# H0AR3_Backend.net
KiCad netlist of a schematic drawn in Altium Designer
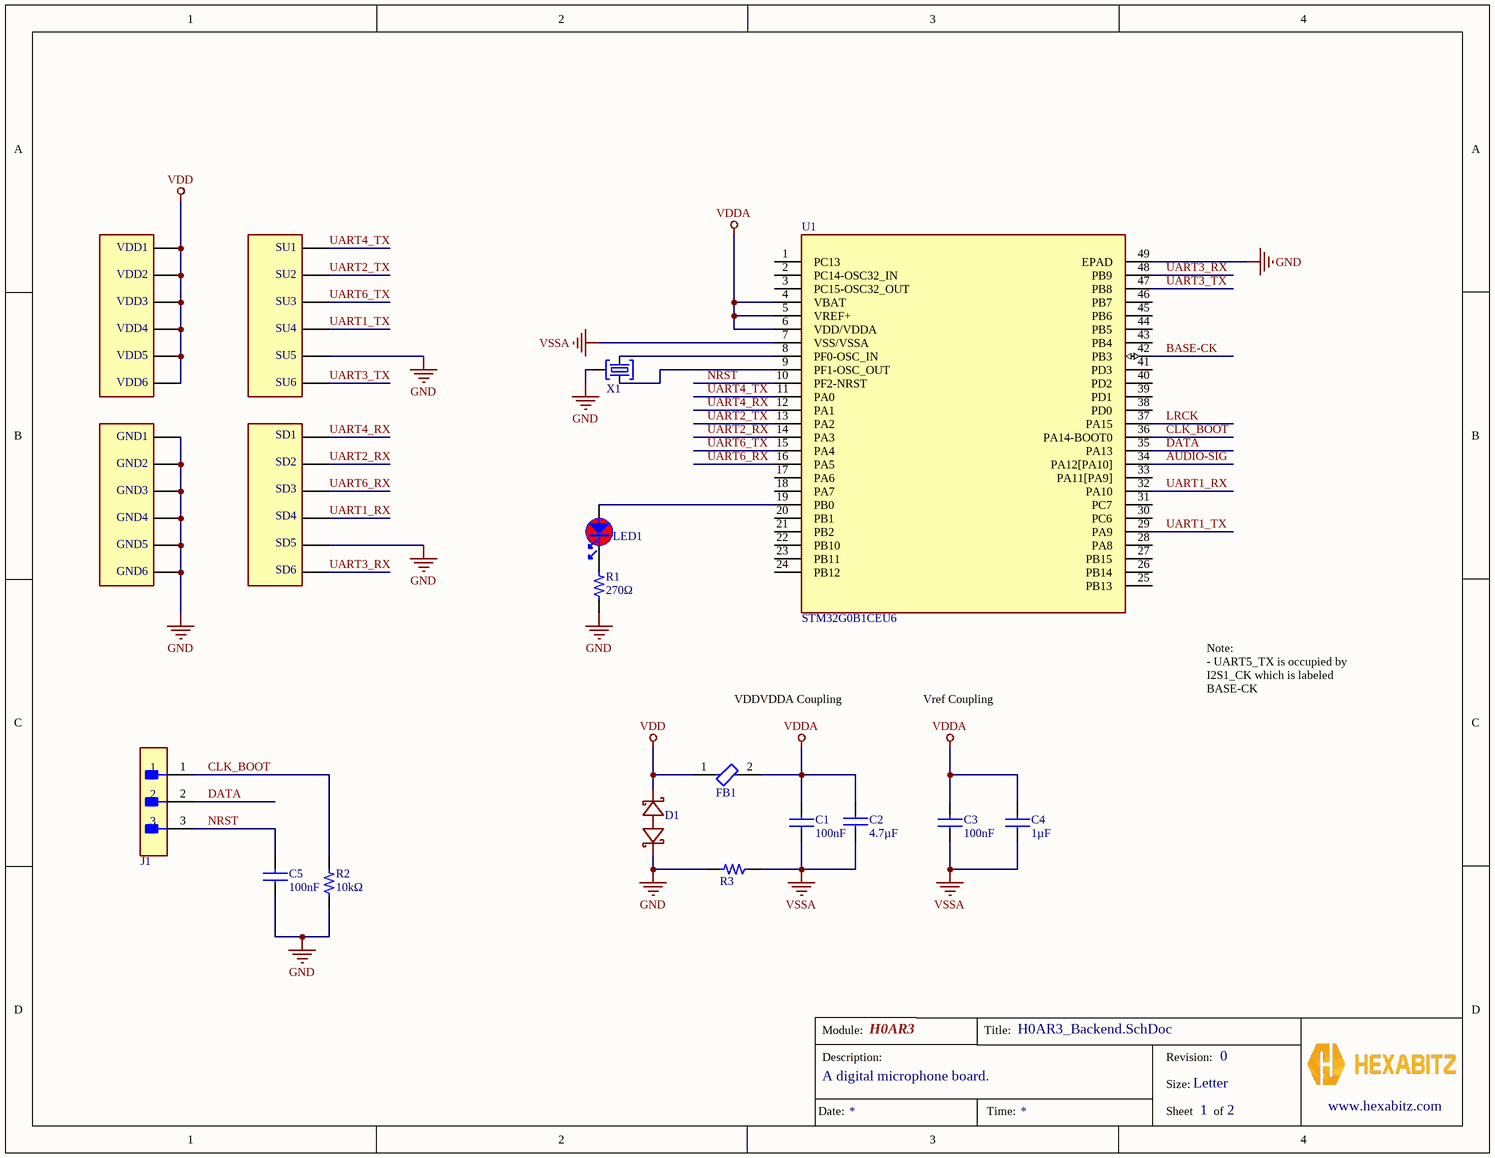
[diagram p0: H0AR3_Backend.SchDoc]

(export (version "E")
  (design (tool "Eeschema 10.0.6"))
  (components
    (comp (ref "C1")
      (value "100nF")
      (footprint "C0603")
      (fields
        (field (name "MANUFACTURER") "Samsung Electro-Mechanics")
        (field (name "MANUFACTURER PART NUMBER") "CL10B104KA8NNNC")
        (field (name "TOLERANCE") "10%")
      )
      (libsource (lib "Hexabitz Altium Library") (part "generic Capacitor"))
    )
    (comp (ref "C2")
      (value "4.7µF")
      (footprint "C0805")
      (fields
        (field (name "MANUFACTURER") "Samsung Electro-Mechanics")
        (field (name "MANUFACTURER PART NUMBER") "CL21X475KAQNNNE")
        (field (name "TOLERANCE") "10%")
      )
      (libsource (lib "Hexabitz Altium Library") (part "generic Capacitor"))
    )
    (comp (ref "C3")
      (value "100nF")
      (footprint "C0603")
      (fields
        (field (name "MANUFACTURER") "Samsung Electro-Mechanics")
        (field (name "MANUFACTURER PART NUMBER") "CL10B104KA8NNNC")
        (field (name "TOLERANCE") "10%")
      )
      (libsource (lib "Hexabitz Altium Library") (part "generic Capacitor"))
    )
    (comp (ref "C4")
      (value "1µF")
      (footprint "C0805")
      (description "Ceramic Capacitor, Ceramic, 16V, 10% +Tol, 10% -Tol, X7R, 15% TC, 1uF, Surface Mount, 0805")
      (fields
        (field (name "MANUFACTURER") "Yageo Group")
        (field (name "MANUFACTURER PART NUMBER") "CC0805KKX7R7BB105")
      )
      (libsource (lib "Hexabitz Altium Library") (part "generic Capacitor"))
    )
    (comp (ref "C5")
      (value "100nF")
      (footprint "C0603")
      (fields
        (field (name "MANUFACTURER") "Samsung Electro-Mechanics")
        (field (name "MANUFACTURER PART NUMBER") "CL10B104KA8NNNC")
        (field (name "TOLERANCE") "10%")
      )
      (libsource (lib "Hexabitz Altium Library") (part "generic Capacitor"))
    )
    (comp (ref "D1")
      (value "CDSOD323-T03SC")
      (footprint "SOD2513X114N")
      (description "A 3V, 350W, bi-directional, standard capacitance, SOD323 pkg TVS Diode ¦ Bourns CDSOD323-T03SC")
      (fields (field (name "MANUFACTURER") "Bourns"))
      (libsource (lib "Hexabitz Altium Library") (part "CDSOD323-T03SC"))
    )
    (comp (ref "FB1")
      (value "MMZ1608Y300B")
      (footprint "FP-MMZ1608-0_8-MFG")
      (description "Ferrite Beads 0603 30ohms 1500mA Signal Line AEC-Q200")
      (fields
        (field (name "MANUFACTURER") "TDK")
        (field (name "MANUFACTURER PART NUMBER") "MMZ1608Y300BTD25")
      )
      (libsource (lib "Hexabitz Altium Library") (part "MMZ1608Y300B"))
    )
    (comp (ref "GND1")
      (value "HEXABIT_UART_PORT")
      (footprint "HEXABIT_POWER_PORT_D")
      (libsource (lib "hexabitz_connectors.Library") (part "HEXABIT_POWER_PORT_D"))
    )
    (comp (ref "GND2")
      (value "HEXABIT_UART_PORT")
      (footprint "HEXABIT_POWER_PORT_D")
      (libsource (lib "hexabitz_connectors.Library") (part "HEXABIT_POWER_PORT_D"))
    )
    (comp (ref "GND3")
      (value "HEXABIT_UART_PORT")
      (footprint "HEXABIT_POWER_PORT_D")
      (libsource (lib "hexabitz_connectors.Library") (part "HEXABIT_POWER_PORT_D"))
    )
    (comp (ref "GND4")
      (value "HEXABIT_UART_PORT")
      (footprint "HEXABIT_POWER_PORT_D")
      (libsource (lib "hexabitz_connectors.Library") (part "HEXABIT_POWER_PORT_D"))
    )
    (comp (ref "GND5")
      (value "HEXABIT_UART_PORT")
      (footprint "HEXABIT_POWER_PORT_D")
      (libsource (lib "hexabitz_connectors.Library") (part "HEXABIT_POWER_PORT_D"))
    )
    (comp (ref "GND6")
      (value "HEXABIT_UART_PORT")
      (footprint "HEXABIT_POWER_PORT_D")
      (libsource (lib "hexabitz_connectors.Library") (part "HEXABIT_POWER_PORT_D"))
    )
    (comp (ref "J1")
      (value "TSW-103-14-G-S")
      (footprint "FP-TSW-103-14-G-S-MFG")
      (description "CONN HEADER VERT 3POS 2.54MM")
      (libsource (lib "Altium Content Vault") (part "cd3439d6ef35ae5d9b27ec4fdd3e828"))
    )
    (comp (ref "LED1")
      (value "VLMS1300-GS08")
      (footprint "FP-6_541-5092_01-4-MFG")
      (description "LED Uni-Color Super Red 639nm 2-Pin Chip 0603(1608Metric) T/R")
      (fields (field (name "MANUFACTURER") "Vishay Semiconductors"))
      (libsource (lib "Hexabitz Altium Library") (part "VLMS1300-GS08"))
    )
    (comp (ref "R1")
      (value "270Ω")
      (footprint "R0603")
      (description "Res Thick Film 0603 270 Ohm 5% 0.1W(1/10W) ±200ppm/C Pad SMD Automotive T/R")
      (fields
        (field (name "MANUFACTURER") "Panasonic")
        (field (name "MANUFACTURER PART NUMBER") "ERJ-3GEYJ271V")
      )
      (libsource (lib "") (part "generic Resistor_2"))
    )
    (comp (ref "R2")
      (value "10kΩ")
      (footprint "R0603")
      (description "100mW Thick Film Resistors ±100ppm/℃ ±1% 10kΩ 0603 Chip Resistor - Surface Mount ROHS")
      (fields
        (field (name "MANUFACTURER") "Yageo Group")
        (field (name "MANUFACTURER PART NUMBER") "RC0603FR-0710KL")
      )
      (libsource (lib "Hexabitz Altium Library") (part "generic Resistor"))
    )
    (comp (ref "R3")
      (value "Manufacturer Part Number")
      (footprint "R0603")
      (libsource (lib "") (part "generic Resistor_1"))
    )
    (comp (ref "SD1")
      (value "HEXABIT_UART_PORT")
      (footprint "HEXABIT_UART_PORT_D")
      (libsource (lib "hexabitz_connectors.Library") (part "HEXABIT_UART_PORT_D"))
    )
    (comp (ref "SD2")
      (value "HEXABIT_UART_PORT")
      (footprint "HEXABIT_UART_PORT_D")
      (libsource (lib "hexabitz_connectors.Library") (part "HEXABIT_UART_PORT_D"))
    )
    (comp (ref "SD3")
      (value "HEXABIT_UART_PORT")
      (footprint "HEXABIT_UART_PORT_D")
      (libsource (lib "hexabitz_connectors.Library") (part "HEXABIT_UART_PORT_D"))
    )
    (comp (ref "SD4")
      (value "HEXABIT_UART_PORT")
      (footprint "HEXABIT_UART_PORT_D")
      (libsource (lib "hexabitz_connectors.Library") (part "HEXABIT_UART_PORT_D"))
    )
    (comp (ref "SD5")
      (value "HEXABIT_UART_PORT")
      (footprint "HEXABIT_UART_PORT_D")
      (libsource (lib "hexabitz_connectors.Library") (part "HEXABIT_UART_PORT_D"))
    )
    (comp (ref "SD6")
      (value "HEXABIT_UART_PORT")
      (footprint "HEXABIT_UART_PORT_D")
      (libsource (lib "hexabitz_connectors.Library") (part "HEXABIT_UART_PORT_D"))
    )
    (comp (ref "SU1")
      (value "HEXABIT_UART_PORT")
      (footprint "HEXABIT_UART_PORT_U")
      (libsource (lib "hexabitz_connectors.Library") (part "HEXABIT_UART_PORT_U"))
    )
    (comp (ref "SU2")
      (value "HEXABIT_UART_PORT")
      (footprint "HEXABIT_UART_PORT_U")
      (libsource (lib "hexabitz_connectors.Library") (part "HEXABIT_UART_PORT_U"))
    )
    (comp (ref "SU3")
      (value "HEXABIT_UART_PORT")
      (footprint "HEXABIT_UART_PORT_U")
      (libsource (lib "hexabitz_connectors.Library") (part "HEXABIT_UART_PORT_U"))
    )
    (comp (ref "SU4")
      (value "HEXABIT_UART_PORT")
      (footprint "HEXABIT_UART_PORT_U")
      (libsource (lib "hexabitz_connectors.Library") (part "HEXABIT_UART_PORT_U"))
    )
    (comp (ref "SU5")
      (value "HEXABIT_UART_PORT")
      (footprint "HEXABIT_UART_PORT_U")
      (libsource (lib "hexabitz_connectors.Library") (part "HEXABIT_UART_PORT_U"))
    )
    (comp (ref "SU6")
      (value "HEXABIT_UART_PORT")
      (footprint "HEXABIT_UART_PORT_U")
      (libsource (lib "hexabitz_connectors.Library") (part "HEXABIT_UART_PORT_U"))
    )
    (comp (ref "U1")
      (value "STM32G0B1CEU6")
      (footprint "QFN50P700X700X65-49N-D")
      (description "MCU 32-bit ARM Cortex M0+ RISC 512KB Flash 1.8V/2.5V/3.3V 48-Pin UFQFPN EP Tray")
      (fields
        (field (name "MANUFACTURER") "STMicroelectronics")
        (field (name "MANUFACTURER PART NUMBER") "STM32G0B1CEU6")
      )
      (libsource (lib "Hexabitz Altium Library") (part "STM32G0B1CEU6"))
    )
    (comp (ref "VDD1")
      (value "HEXABIT_UART_PORT")
      (footprint "HEXABIT_POWER_PORT_U")
      (libsource (lib "hexabitz_connectors.Library") (part "HEXABIT_POWER_PORT_U"))
    )
    (comp (ref "VDD2")
      (value "HEXABIT_UART_PORT")
      (footprint "HEXABIT_POWER_PORT_U")
      (libsource (lib "hexabitz_connectors.Library") (part "HEXABIT_POWER_PORT_U"))
    )
    (comp (ref "VDD3")
      (value "HEXABIT_UART_PORT")
      (footprint "HEXABIT_POWER_PORT_U")
      (libsource (lib "hexabitz_connectors.Library") (part "HEXABIT_POWER_PORT_U"))
    )
    (comp (ref "VDD4")
      (value "HEXABIT_UART_PORT")
      (footprint "HEXABIT_POWER_PORT_U")
      (libsource (lib "hexabitz_connectors.Library") (part "HEXABIT_POWER_PORT_U"))
    )
    (comp (ref "VDD5")
      (value "HEXABIT_UART_PORT")
      (footprint "HEXABIT_POWER_PORT_U")
      (libsource (lib "hexabitz_connectors.Library") (part "HEXABIT_POWER_PORT_U"))
    )
    (comp (ref "VDD6")
      (value "HEXABIT_UART_PORT")
      (footprint "HEXABIT_POWER_PORT_U")
      (libsource (lib "hexabitz_connectors.Library") (part "HEXABIT_POWER_PORT_U"))
    )
    (comp (ref "X1")
      (value "CSTCE8M00G52Z-R0")
      (footprint "XTALL_CSTCE8M00G52")
      (description "Ceramic Resonator 8MHz ±0.5% (Tol) ±0.2% (Stability) 10pF 40Ohm 3-Pin CSMD T/R")
      (fields (field (name "MANUFACTURER") "Murata") (field (name "TOLERANCE") "0.5%"))
      (libsource (lib "Hexabitz Altium Library") (part "CSTCE8M00G52Z-R0"))
    )
  )
  (nets
    (net (code "1") (name "/AUDIO-SIG") (class "Default")
      (node (ref "U1") (pin "34") (pinfunction "PA12[PA10]_34") (pintype "passive"))
    )
    (net (code "2") (name "/BASE-CK") (class "Default")
      (node (ref "U1") (pin "42") (pinfunction "PB3_42") (pintype "bidirectional"))
    )
    (net (code "3") (name "/CLK_BOOT") (class "Default")
      (node (ref "J1") (pin "1") (pinfunction "1_1") (pintype "passive"))
      (node (ref "R2") (pin "1") (pinfunction "1_1") (pintype "passive"))
      (node (ref "U1") (pin "36") (pinfunction "PA14-BOOT0_36") (pintype "passive"))
    )
    (net (code "4") (name "/DATA") (class "Default")
      (node (ref "J1") (pin "2") (pinfunction "2_2") (pintype "passive"))
      (node (ref "U1") (pin "35") (pinfunction "PA13_35") (pintype "passive"))
    )
    (net (code "5") (name "/LRCK") (class "Default")
      (node (ref "U1") (pin "37") (pinfunction "PA15_37") (pintype "passive"))
    )
    (net (code "6") (name "/NRST") (class "Default")
      (node (ref "C5") (pin "2") (pinfunction "2_2") (pintype "passive"))
      (node (ref "J1") (pin "3") (pinfunction "3_3") (pintype "passive"))
      (node (ref "U1") (pin "10") (pinfunction "PF2-NRST_10") (pintype "passive"))
    )
    (net (code "7") (name "/UART1_RX") (class "Default")
      (node (ref "SD4") (pin "UART_D") (pinfunction "UART_D_UART_D") (pintype "passive"))
      (node (ref "U1") (pin "32") (pinfunction "PA10_32") (pintype "passive"))
    )
    (net (code "8") (name "/UART1_TX") (class "Default")
      (node (ref "SU4") (pin "UART_U") (pinfunction "UART_U_UART_U") (pintype "passive"))
      (node (ref "U1") (pin "29") (pinfunction "PA9_29") (pintype "passive"))
    )
    (net (code "9") (name "/UART2_RX") (class "Default")
      (node (ref "SD2") (pin "UART_D") (pinfunction "UART_D_UART_D") (pintype "passive"))
      (node (ref "U1") (pin "14") (pinfunction "PA3_14") (pintype "passive"))
    )
    (net (code "10") (name "/UART2_TX") (class "Default")
      (node (ref "SU2") (pin "UART_U") (pinfunction "UART_U_UART_U") (pintype "passive"))
      (node (ref "U1") (pin "13") (pinfunction "PA2_13") (pintype "passive"))
    )
    (net (code "11") (name "/UART3_RX") (class "Default")
      (node (ref "SD6") (pin "UART_D") (pinfunction "UART_D_UART_D") (pintype "passive"))
      (node (ref "U1") (pin "48") (pinfunction "PB9_48") (pintype "passive"))
    )
    (net (code "12") (name "/UART3_TX") (class "Default")
      (node (ref "SU6") (pin "UART_U") (pinfunction "UART_U_UART_U") (pintype "passive"))
      (node (ref "U1") (pin "47") (pinfunction "PB8_47") (pintype "passive"))
    )
    (net (code "13") (name "/UART4_RX") (class "Default")
      (node (ref "SD1") (pin "UART_D") (pinfunction "UART_D_UART_D") (pintype "passive"))
      (node (ref "U1") (pin "12") (pinfunction "PA1_12") (pintype "passive"))
    )
    (net (code "14") (name "/UART4_TX") (class "Default")
      (node (ref "SU1") (pin "UART_U") (pinfunction "UART_U_UART_U") (pintype "passive"))
      (node (ref "U1") (pin "11") (pinfunction "PA0_11") (pintype "passive"))
    )
    (net (code "15") (name "/UART6_RX") (class "Default")
      (node (ref "SD3") (pin "UART_D") (pinfunction "UART_D_UART_D") (pintype "passive"))
      (node (ref "U1") (pin "16") (pinfunction "PA5_16") (pintype "passive"))
    )
    (net (code "16") (name "/UART6_TX") (class "Default")
      (node (ref "SU3") (pin "UART_U") (pinfunction "UART_U_UART_U") (pintype "passive"))
      (node (ref "U1") (pin "15") (pinfunction "PA4_15") (pintype "passive"))
    )
    (net (code "17") (name "GND") (class "Default")
      (node (ref "C5") (pin "1") (pinfunction "1_1") (pintype "passive"))
      (node (ref "D1") (pin "1") (pinfunction "A_1") (pintype "passive"))
      (node (ref "GND1") (pin "Pwr_D") (pinfunction "Pwr_D_Pwr_D") (pintype "passive"))
      (node (ref "GND2") (pin "Pwr_D") (pinfunction "Pwr_D_Pwr_D") (pintype "passive"))
      (node (ref "GND3") (pin "Pwr_D") (pinfunction "Pwr_D_Pwr_D") (pintype "passive"))
      (node (ref "GND4") (pin "Pwr_D") (pinfunction "Pwr_D_Pwr_D") (pintype "passive"))
      (node (ref "GND5") (pin "Pwr_D") (pinfunction "Pwr_D_Pwr_D") (pintype "passive"))
      (node (ref "GND6") (pin "Pwr_D") (pinfunction "Pwr_D_Pwr_D") (pintype "passive"))
      (node (ref "R1") (pin "1") (pinfunction "1_1") (pintype "passive"))
      (node (ref "R2") (pin "2") (pinfunction "2_2") (pintype "passive"))
      (node (ref "R3") (pin "1") (pinfunction "1_1") (pintype "passive"))
      (node (ref "SD5") (pin "UART_D") (pinfunction "UART_D_UART_D") (pintype "passive"))
      (node (ref "SU5") (pin "UART_U") (pinfunction "UART_U_UART_U") (pintype "passive"))
      (node (ref "U1") (pin "49") (pinfunction "EPAD_49") (pintype "passive"))
      (node (ref "X1") (pin "P$2") (pinfunction "2_P$2") (pintype "passive"))
    )
    (net (code "18") (name "Net-(LED1-Pad1)") (class "Default")
      (node (ref "LED1") (pin "1") (pintype "passive"))
      (node (ref "R1") (pin "2") (pinfunction "2_2") (pintype "passive"))
    )
    (net (code "19") (name "Net-(U1-PB0)") (class "Default")
      (node (ref "LED1") (pin "2") (pintype "passive"))
      (node (ref "U1") (pin "19") (pinfunction "PB0_19") (pintype "passive"))
    )
    (net (code "20") (name "Net-(U1-PF0-OSC_IN)") (class "Default")
      (node (ref "U1") (pin "8") (pinfunction "PF0-OSC_IN_8") (pintype "passive"))
      (node (ref "X1") (pin "P$3") (pinfunction "3_P$3") (pintype "passive"))
    )
    (net (code "21") (name "Net-(U1-PF1-OSC_OUT)") (class "Default")
      (node (ref "U1") (pin "9") (pinfunction "PF1-OSC_OUT_9") (pintype "passive"))
      (node (ref "X1") (pin "P$1") (pinfunction "1_P$1") (pintype "passive"))
    )
    (net (code "22") (name "VDD") (class "Default")
      (node (ref "D1") (pin "2") (pinfunction "C_2") (pintype "passive"))
      (node (ref "FB1") (pin "1") (pinfunction "1_1") (pintype "passive"))
      (node (ref "VDD1") (pin "Pwr_U") (pinfunction "Pwr_U_Pwr_U") (pintype "passive"))
      (node (ref "VDD2") (pin "Pwr_U") (pinfunction "Pwr_U_Pwr_U") (pintype "passive"))
      (node (ref "VDD3") (pin "Pwr_U") (pinfunction "Pwr_U_Pwr_U") (pintype "passive"))
      (node (ref "VDD4") (pin "Pwr_U") (pinfunction "Pwr_U_Pwr_U") (pintype "passive"))
      (node (ref "VDD5") (pin "Pwr_U") (pinfunction "Pwr_U_Pwr_U") (pintype "passive"))
      (node (ref "VDD6") (pin "Pwr_U") (pinfunction "Pwr_U_Pwr_U") (pintype "passive"))
    )
    (net (code "23") (name "VDDA") (class "Default")
      (node (ref "C1") (pin "2") (pinfunction "2_2") (pintype "passive"))
      (node (ref "C2") (pin "1") (pinfunction "1_1") (pintype "passive"))
      (node (ref "C3") (pin "2") (pinfunction "2_2") (pintype "passive"))
      (node (ref "C4") (pin "2") (pinfunction "2_2") (pintype "passive"))
      (node (ref "FB1") (pin "2") (pinfunction "2_2") (pintype "passive"))
      (node (ref "U1") (pin "4") (pinfunction "VBAT_4") (pintype "passive"))
      (node (ref "U1") (pin "5") (pinfunction "VREF+_5") (pintype "passive"))
      (node (ref "U1") (pin "6") (pinfunction "VDD/VDDA_6") (pintype "passive"))
    )
    (net (code "24") (name "VSSA") (class "Default")
      (node (ref "C1") (pin "1") (pinfunction "1_1") (pintype "passive"))
      (node (ref "C2") (pin "2") (pinfunction "2_2") (pintype "passive"))
      (node (ref "C3") (pin "1") (pinfunction "1_1") (pintype "passive"))
      (node (ref "C4") (pin "1") (pinfunction "1_1") (pintype "passive"))
      (node (ref "R3") (pin "2") (pinfunction "2_2") (pintype "passive"))
      (node (ref "U1") (pin "7") (pinfunction "VSS/VSSA_7") (pintype "passive"))
    )
    (net (code "25") (name "unconnected-(U1-PA6-Pad17)") (class "Default")
      (node (ref "U1") (pin "17") (pinfunction "PA6_17") (pintype "passive"))
    )
    (net (code "26") (name "unconnected-(U1-PA7-Pad18)") (class "Default")
      (node (ref "U1") (pin "18") (pinfunction "PA7_18") (pintype "passive"))
    )
    (net (code "27") (name "unconnected-(U1-PA8-Pad28)") (class "Default")
      (node (ref "U1") (pin "28") (pinfunction "PA8_28") (pintype "passive"))
    )
    (net (code "28") (name "unconnected-(U1-PA11[PA9]-Pad33)") (class "Default")
      (node (ref "U1") (pin "33") (pinfunction "PA11[PA9]_33") (pintype "passive"))
    )
    (net (code "29") (name "unconnected-(U1-PB1-Pad20)") (class "Default")
      (node (ref "U1") (pin "20") (pinfunction "PB1_20") (pintype "passive"))
    )
    (net (code "30") (name "unconnected-(U1-PB2-Pad21)") (class "Default")
      (node (ref "U1") (pin "21") (pinfunction "PB2_21") (pintype "passive"))
    )
    (net (code "31") (name "unconnected-(U1-PB4-Pad43)") (class "Default")
      (node (ref "U1") (pin "43") (pinfunction "PB4_43") (pintype "passive"))
    )
    (net (code "32") (name "unconnected-(U1-PB5-Pad44)") (class "Default")
      (node (ref "U1") (pin "44") (pinfunction "PB5_44") (pintype "passive"))
    )
    (net (code "33") (name "unconnected-(U1-PB6-Pad45)") (class "Default")
      (node (ref "U1") (pin "45") (pinfunction "PB6_45") (pintype "passive"))
    )
    (net (code "34") (name "unconnected-(U1-PB7-Pad46)") (class "Default")
      (node (ref "U1") (pin "46") (pinfunction "PB7_46") (pintype "passive"))
    )
    (net (code "35") (name "unconnected-(U1-PB10-Pad22)") (class "Default")
      (node (ref "U1") (pin "22") (pinfunction "PB10_22") (pintype "passive"))
    )
    (net (code "36") (name "unconnected-(U1-PB11-Pad23)") (class "Default")
      (node (ref "U1") (pin "23") (pinfunction "PB11_23") (pintype "passive"))
    )
    (net (code "37") (name "unconnected-(U1-PB12-Pad24)") (class "Default")
      (node (ref "U1") (pin "24") (pinfunction "PB12_24") (pintype "passive"))
    )
    (net (code "38") (name "unconnected-(U1-PB13-Pad25)") (class "Default")
      (node (ref "U1") (pin "25") (pinfunction "PB13_25") (pintype "passive"))
    )
    (net (code "39") (name "unconnected-(U1-PB14-Pad26)") (class "Default")
      (node (ref "U1") (pin "26") (pinfunction "PB14_26") (pintype "passive"))
    )
    (net (code "40") (name "unconnected-(U1-PB15-Pad27)") (class "Default")
      (node (ref "U1") (pin "27") (pinfunction "PB15_27") (pintype "passive"))
    )
    (net (code "41") (name "unconnected-(U1-PC6-Pad30)") (class "Default")
      (node (ref "U1") (pin "30") (pinfunction "PC6_30") (pintype "passive"))
    )
    (net (code "42") (name "unconnected-(U1-PC7-Pad31)") (class "Default")
      (node (ref "U1") (pin "31") (pinfunction "PC7_31") (pintype "passive"))
    )
    (net (code "43") (name "unconnected-(U1-PC13-Pad1)") (class "Default")
      (node (ref "U1") (pin "1") (pinfunction "PC13_1") (pintype "passive"))
    )
    (net (code "44") (name "unconnected-(U1-PC14-OSC32_IN-Pad2)") (class "Default")
      (node (ref "U1") (pin "2") (pinfunction "PC14-OSC32_IN_2") (pintype "passive"))
    )
    (net (code "45") (name "unconnected-(U1-PC15-OSC32_OUT-Pad3)") (class "Default")
      (node (ref "U1") (pin "3") (pinfunction "PC15-OSC32_OUT_3") (pintype "passive"))
    )
    (net (code "46") (name "unconnected-(U1-PD0-Pad38)") (class "Default")
      (node (ref "U1") (pin "38") (pinfunction "PD0_38") (pintype "passive"))
    )
    (net (code "47") (name "unconnected-(U1-PD1-Pad39)") (class "Default")
      (node (ref "U1") (pin "39") (pinfunction "PD1_39") (pintype "passive"))
    )
    (net (code "48") (name "unconnected-(U1-PD2-Pad40)") (class "Default")
      (node (ref "U1") (pin "40") (pinfunction "PD2_40") (pintype "passive"))
    )
    (net (code "49") (name "unconnected-(U1-PD3-Pad41)") (class "Default")
      (node (ref "U1") (pin "41") (pinfunction "PD3_41") (pintype "passive"))
    )
  )
)
